# Main.net
KiCad netlist of a schematic drawn in Altium Designer
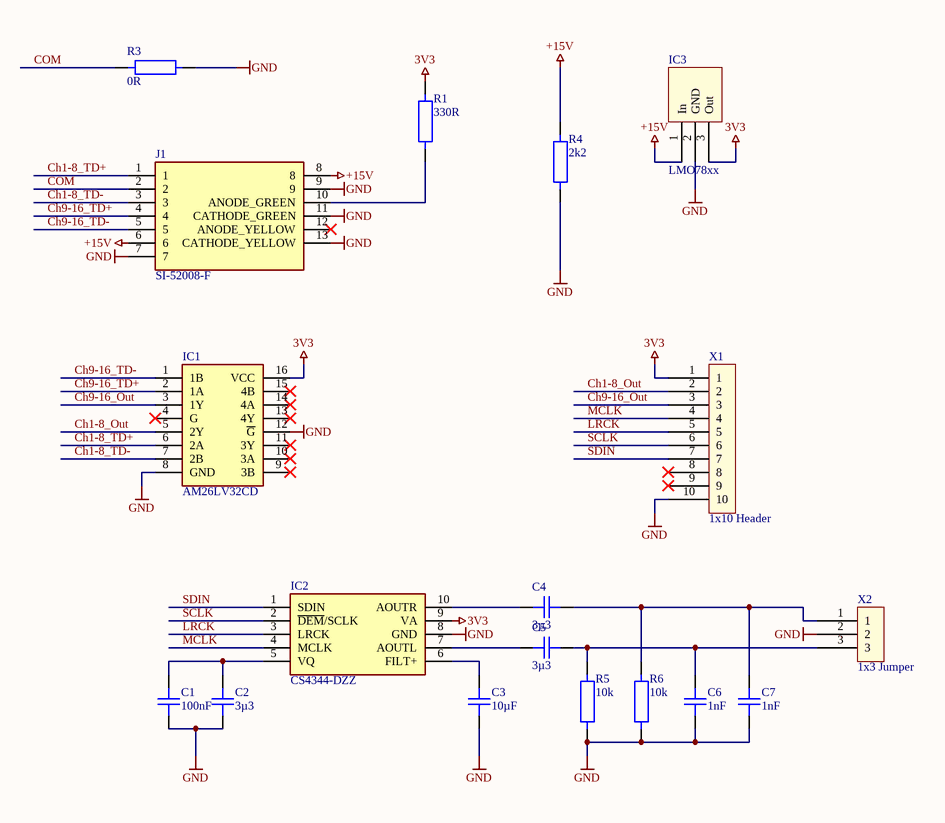
[diagram p0: Main.SchDoc]

(export (version "E")
  (design (tool "Eeschema 10.0.6"))
  (components
    (comp (ref "C1")
      (value "100nF")
      (footprint "1206")
      (description "1206_C")
      (libsource (lib "FPGA_Board_Library") (part "1206_C_1nF/63V"))
    )
    (comp (ref "C2")
      (value "3µ3")
      (footprint "1206")
      (description "1206_C")
      (libsource (lib "FPGA_Board_Library") (part "1206_C_1nF/63V"))
    )
    (comp (ref "C3")
      (value "10µF")
      (footprint "1206")
      (description "1206_C")
      (libsource (lib "FPGA_Board_Library") (part "1206_C_1nF/63V"))
    )
    (comp (ref "C4")
      (value "3µ3")
      (footprint "1206")
      (description "1206_C")
      (libsource (lib "FPGA_Board_Library") (part "1206_C_1nF/63V"))
    )
    (comp (ref "C5")
      (value "3µ3")
      (footprint "1206")
      (description "1206_C")
      (libsource (lib "FPGA_Board_Library") (part "1206_C_1nF/63V"))
    )
    (comp (ref "C6")
      (value "1nF")
      (footprint "1206")
      (description "1206_C")
      (libsource (lib "FPGA_Board_Library") (part "1206_C_1nF/63V"))
    )
    (comp (ref "C7")
      (value "1nF")
      (footprint "1206")
      (description "1206_C")
      (libsource (lib "FPGA_Board_Library") (part "1206_C_1nF/63V"))
    )
    (comp (ref "IC1")
      (value "AM26LV32CD")
      (footprint "SOIC127P600X175-16N")
      (description "Low-Voltage High-Speed Quadruple Differential Line Receiver")
      (fields (field (name "MOUSER PART NUMBER") "595-AM26LV32CD"))
      (libsource (lib "FPGA_AudioMischpult") (part "AM26LV32CD"))
    )
    (comp (ref "IC2")
      (value "CS4344-DZZ")
      (footprint "SOP50P490X110-10N")
      (description "Audio D/A Converter ICs Stereo DAC 24-Bit 192kHz")
      (fields (field (name "MOUSER PART NUMBER") "777-CS4344-DZZ"))
      (libsource (lib "FPGA_AudioMischpult") (part "CS4344-DZZ"))
    )
    (comp (ref "IC3")
      (value "LMO78xx")
      (footprint "LMO78xx")
      (libsource (lib "KDEE_HiResPG") (part "LMO78xx"))
    )
    (comp (ref "J1")
      (value "SI-52008-F")
      (footprint "SI-52007-F_1")
      (description "Magjack 10BASE T POE with LEDS Bel-Stewart RJ Socket Module, STP, Straight")
      (fields (field (name "MOUSER PART NUMBER") "530-SI-52008-F"))
      (libsource (lib "FPGA_AudioMischpult") (part "SI-52008-F"))
    )
    (comp (ref "R1")
      (value "330R")
      (footprint "1206")
      (description "1206_R")
      (libsource (lib "FPGA_Board_Library") (part "1206_R"))
    )
    (comp (ref "R3")
      (value "0R")
      (footprint "1206")
      (description "1206_R")
      (libsource (lib "FPGA_Board_Library") (part "1206_R"))
    )
    (comp (ref "R4")
      (value "2k2")
      (footprint "1206")
      (description "1206_R")
      (libsource (lib "FPGA_Board_Library") (part "1206_R"))
    )
    (comp (ref "R5")
      (value "10k")
      (footprint "1206")
      (description "1206_R")
      (libsource (lib "FPGA_Board_Library") (part "1206_R"))
    )
    (comp (ref "R6")
      (value "10k")
      (footprint "1206")
      (description "1206_R")
      (libsource (lib "FPGA_Board_Library") (part "1206_R"))
    )
    (comp (ref "X1")
      (value "1x10 Header")
      (footprint "1x10 Header")
      (libsource (lib "KDEE_HiResPG") (part "1x10 Header"))
    )
    (comp (ref "X2")
      (value "1x3 Jumper")
      (footprint "1x3 Jumper")
      (libsource (lib "KDEE_HiResPG") (part "1x3 Jumper"))
    )
  )
  (nets
    (net (code "1") (name "+15V") (class "Default")
      (node (ref "IC3") (pin "1") (pinfunction "In_1") (pintype "passive"))
      (node (ref "J1") (pin "6") (pinfunction "6_6") (pintype "passive"))
      (node (ref "J1") (pin "8") (pinfunction "8_8") (pintype "passive"))
      (node (ref "R4") (pin "2") (pinfunction "2_2") (pintype "passive"))
    )
    (net (code "2") (name "/COM") (class "Default")
      (node (ref "J1") (pin "2") (pinfunction "2_2") (pintype "passive"))
      (node (ref "R3") (pin "1") (pinfunction "1_1") (pintype "passive"))
    )
    (net (code "3") (name "/Ch1-8_Out") (class "Default")
      (node (ref "IC1") (pin "5") (pinfunction "2Y_5") (pintype "passive"))
      (node (ref "X1") (pin "2") (pinfunction "2_2") (pintype "passive"))
    )
    (net (code "4") (name "/Ch1-8_TD+") (class "Default")
      (node (ref "IC1") (pin "6") (pinfunction "2A_6") (pintype "passive"))
      (node (ref "J1") (pin "1") (pinfunction "1_1") (pintype "passive"))
    )
    (net (code "5") (name "/Ch1-8_TD-") (class "Default")
      (node (ref "IC1") (pin "7") (pinfunction "2B_7") (pintype "passive"))
      (node (ref "J1") (pin "3") (pinfunction "3_3") (pintype "passive"))
    )
    (net (code "6") (name "/Ch9-16_Out") (class "Default")
      (node (ref "IC1") (pin "3") (pinfunction "1Y_3") (pintype "passive"))
      (node (ref "X1") (pin "3") (pinfunction "3_3") (pintype "passive"))
    )
    (net (code "7") (name "/Ch9-16_TD+") (class "Default")
      (node (ref "IC1") (pin "2") (pinfunction "1A_2") (pintype "passive"))
      (node (ref "J1") (pin "4") (pinfunction "4_4") (pintype "passive"))
    )
    (net (code "8") (name "/Ch9-16_TD-") (class "Default")
      (node (ref "IC1") (pin "1") (pinfunction "1B_1") (pintype "passive"))
      (node (ref "J1") (pin "5") (pinfunction "5_5") (pintype "passive"))
    )
    (net (code "9") (name "/LRCK") (class "Default")
      (node (ref "IC2") (pin "3") (pinfunction "LRCK_3") (pintype "passive"))
      (node (ref "X1") (pin "5") (pinfunction "5_5") (pintype "passive"))
    )
    (net (code "10") (name "/MCLK") (class "Default")
      (node (ref "IC2") (pin "4") (pinfunction "MCLK_4") (pintype "passive"))
      (node (ref "X1") (pin "4") (pinfunction "4_4") (pintype "passive"))
    )
    (net (code "11") (name "/SCLK") (class "Default")
      (node (ref "IC2") (pin "2") (pinfunction "~{DEM}/SCLK_2") (pintype "passive"))
      (node (ref "X1") (pin "6") (pinfunction "6_6") (pintype "passive"))
    )
    (net (code "12") (name "/SDIN") (class "Default")
      (node (ref "IC2") (pin "1") (pinfunction "SDIN_1") (pintype "passive"))
      (node (ref "X1") (pin "7") (pinfunction "7_7") (pintype "passive"))
    )
    (net (code "13") (name "3V3") (class "Default")
      (node (ref "IC1") (pin "16") (pinfunction "VCC_16") (pintype "passive"))
      (node (ref "IC2") (pin "9") (pinfunction "VA_9") (pintype "passive"))
      (node (ref "IC3") (pin "3") (pinfunction "Out_3") (pintype "passive"))
      (node (ref "R1") (pin "2") (pinfunction "2_2") (pintype "passive"))
      (node (ref "X1") (pin "1") (pinfunction "1_1") (pintype "passive"))
    )
    (net (code "14") (name "GND") (class "Default")
      (node (ref "C1") (pin "1") (pinfunction "1_1") (pintype "passive"))
      (node (ref "C2") (pin "1") (pinfunction "1_1") (pintype "passive"))
      (node (ref "C3") (pin "2") (pinfunction "2_2") (pintype "passive"))
      (node (ref "C6") (pin "1") (pinfunction "1_1") (pintype "passive"))
      (node (ref "C7") (pin "1") (pinfunction "1_1") (pintype "passive"))
      (node (ref "IC1") (pin "12") (pinfunction "~{G}_12") (pintype "passive"))
      (node (ref "IC1") (pin "8") (pinfunction "GND_8") (pintype "passive"))
      (node (ref "IC2") (pin "8") (pinfunction "GND_8") (pintype "passive"))
      (node (ref "IC3") (pin "2") (pinfunction "GND_2") (pintype "passive"))
      (node (ref "J1") (pin "11") (pinfunction "CATHODE_GREEN_11") (pintype "passive"))
      (node (ref "J1") (pin "13") (pinfunction "CATHODE_YELLOW_13") (pintype "passive"))
      (node (ref "J1") (pin "7") (pinfunction "7_7") (pintype "passive"))
      (node (ref "J1") (pin "9") (pinfunction "9_9") (pintype "passive"))
      (node (ref "R3") (pin "2") (pinfunction "2_2") (pintype "passive"))
      (node (ref "R4") (pin "1") (pinfunction "1_1") (pintype "passive"))
      (node (ref "R5") (pin "1") (pinfunction "1_1") (pintype "passive"))
      (node (ref "R6") (pin "1") (pinfunction "1_1") (pintype "passive"))
      (node (ref "X1") (pin "10") (pinfunction "10_10") (pintype "passive"))
      (node (ref "X2") (pin "2") (pinfunction "2_2") (pintype "passive"))
    )
    (net (code "15") (name "Net-(C4-Pad2)") (class "Default")
      (node (ref "C4") (pin "2") (pinfunction "2_2") (pintype "passive"))
      (node (ref "C7") (pin "2") (pinfunction "2_2") (pintype "passive"))
      (node (ref "R6") (pin "2") (pinfunction "2_2") (pintype "passive"))
      (node (ref "X2") (pin "1") (pinfunction "1_1") (pintype "passive"))
    )
    (net (code "16") (name "Net-(C5-Pad2)") (class "Default")
      (node (ref "C5") (pin "2") (pinfunction "2_2") (pintype "passive"))
      (node (ref "C6") (pin "2") (pinfunction "2_2") (pintype "passive"))
      (node (ref "R5") (pin "2") (pinfunction "2_2") (pintype "passive"))
      (node (ref "X2") (pin "3") (pinfunction "3_3") (pintype "passive"))
    )
    (net (code "17") (name "Net-(IC2-AOUTL)") (class "Default")
      (node (ref "C5") (pin "1") (pinfunction "1_1") (pintype "passive"))
      (node (ref "IC2") (pin "7") (pinfunction "AOUTL_7") (pintype "passive"))
    )
    (net (code "18") (name "Net-(IC2-AOUTR)") (class "Default")
      (node (ref "C4") (pin "1") (pinfunction "1_1") (pintype "passive"))
      (node (ref "IC2") (pin "10") (pinfunction "AOUTR_10") (pintype "passive"))
    )
    (net (code "19") (name "Net-(IC2-FILT+)") (class "Default")
      (node (ref "C3") (pin "1") (pinfunction "1_1") (pintype "passive"))
      (node (ref "IC2") (pin "6") (pinfunction "FILT+_6") (pintype "passive"))
    )
    (net (code "20") (name "Net-(IC2-VQ)") (class "Default")
      (node (ref "C1") (pin "2") (pinfunction "2_2") (pintype "passive"))
      (node (ref "C2") (pin "2") (pinfunction "2_2") (pintype "passive"))
      (node (ref "IC2") (pin "5") (pinfunction "VQ_5") (pintype "passive"))
    )
    (net (code "21") (name "Net-(J1-ANODE_GREEN)") (class "Default")
      (node (ref "J1") (pin "10") (pinfunction "ANODE_GREEN_10") (pintype "passive"))
      (node (ref "R1") (pin "1") (pinfunction "1_1") (pintype "passive"))
    )
    (net (code "22") (name "unconnected-(IC1-3A-Pad10)") (class "Default")
      (node (ref "IC1") (pin "10") (pinfunction "3A_10") (pintype "passive+no_connect"))
    )
    (net (code "23") (name "unconnected-(IC1-3B-Pad9)") (class "Default")
      (node (ref "IC1") (pin "9") (pinfunction "3B_9") (pintype "passive+no_connect"))
    )
    (net (code "24") (name "unconnected-(IC1-3Y-Pad11)") (class "Default")
      (node (ref "IC1") (pin "11") (pinfunction "3Y_11") (pintype "passive+no_connect"))
    )
    (net (code "25") (name "unconnected-(IC1-4A-Pad14)") (class "Default")
      (node (ref "IC1") (pin "14") (pinfunction "4A_14") (pintype "passive+no_connect"))
    )
    (net (code "26") (name "unconnected-(IC1-4B-Pad15)") (class "Default")
      (node (ref "IC1") (pin "15") (pinfunction "4B_15") (pintype "passive+no_connect"))
    )
    (net (code "27") (name "unconnected-(IC1-4Y-Pad13)") (class "Default")
      (node (ref "IC1") (pin "13") (pinfunction "4Y_13") (pintype "passive+no_connect"))
    )
    (net (code "28") (name "unconnected-(IC1-G-Pad4)") (class "Default")
      (node (ref "IC1") (pin "4") (pinfunction "G_4") (pintype "passive+no_connect"))
    )
    (net (code "29") (name "unconnected-(J1-ANODE_YELLOW-Pad12)") (class "Default")
      (node (ref "J1") (pin "12") (pinfunction "ANODE_YELLOW_12") (pintype "passive+no_connect"))
    )
    (net (code "30") (name "unconnected-(X1-Pad8)") (class "Default")
      (node (ref "X1") (pin "8") (pinfunction "8_8") (pintype "passive+no_connect"))
    )
    (net (code "31") (name "unconnected-(X1-Pad9)") (class "Default")
      (node (ref "X1") (pin "9") (pinfunction "9_9") (pintype "passive+no_connect"))
    )
  )
)
